# Smarty-TOP.net
KiCad netlist of a schematic drawn in EAGLE
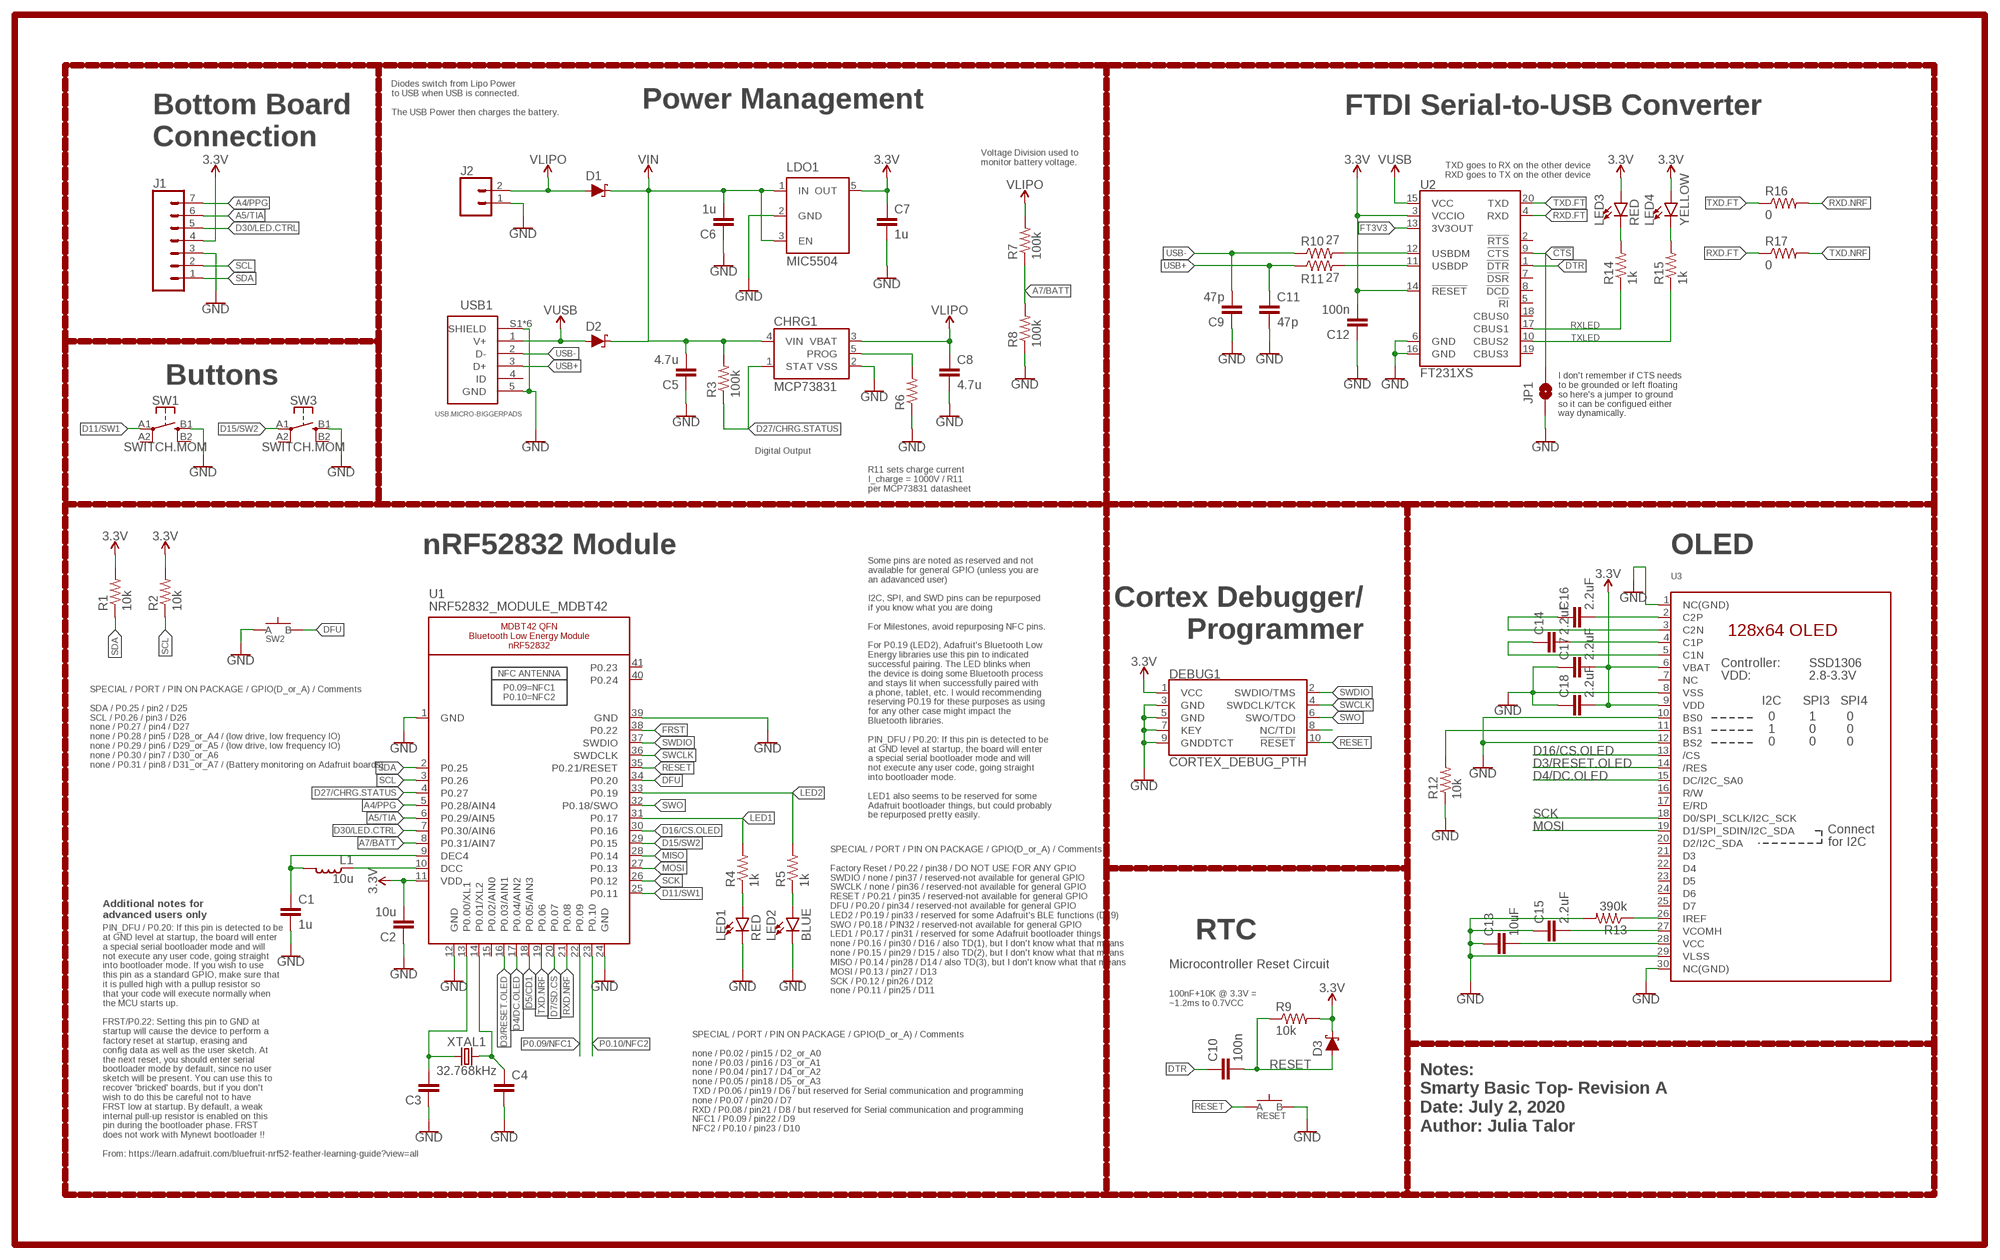
[diagram p0: schematic, sheet 1]

(export (version "E")
  (design (tool "Eeschema 10.0.6"))
  (components
    (comp (ref "C1")
      (value "1u")
      (footprint "eagle-import:C0603")
      (libsource (lib "eagle-import") (part "CAPACITOR0603"))
    )
    (comp (ref "C2")
      (value "10u")
      (footprint "eagle-import:C0805")
      (libsource (lib "eagle-import") (part "CAPACITOR0805"))
    )
    (comp (ref "C3")
      (value "CAPACITOR0603")
      (footprint "eagle-import:C0603")
      (libsource (lib "eagle-import") (part "CAPACITOR0603"))
    )
    (comp (ref "C4")
      (value "CAPACITOR0603")
      (footprint "eagle-import:C0603")
      (libsource (lib "eagle-import") (part "CAPACITOR0603"))
    )
    (comp (ref "C5")
      (value "4.7u")
      (footprint "eagle-import:C0603")
      (libsource (lib "eagle-import") (part "CAPACITOR0603"))
    )
    (comp (ref "C6")
      (value "1u")
      (footprint "eagle-import:C0603")
      (libsource (lib "eagle-import") (part "CAPACITOR0603"))
    )
    (comp (ref "C7")
      (value "1u")
      (footprint "eagle-import:C0603")
      (libsource (lib "eagle-import") (part "CAPACITOR0603"))
    )
    (comp (ref "C8")
      (value "4.7u")
      (footprint "eagle-import:C0603")
      (libsource (lib "eagle-import") (part "CAPACITOR0603"))
    )
    (comp (ref "C9")
      (value "47p")
      (footprint "eagle-import:C0603")
      (libsource (lib "eagle-import") (part "CAPACITOR0603"))
    )
    (comp (ref "C10")
      (value "100n")
      (footprint "eagle-import:C0603")
      (libsource (lib "eagle-import") (part "CAPACITOR0603"))
    )
    (comp (ref "C11")
      (value "47p")
      (footprint "eagle-import:C0603")
      (libsource (lib "eagle-import") (part "CAPACITOR0603"))
    )
    (comp (ref "C12")
      (value "100n")
      (footprint "eagle-import:C0603")
      (libsource (lib "eagle-import") (part "CAPACITOR0603"))
    )
    (comp (ref "C13")
      (value "10uF")
      (footprint "eagle-import:C0603")
      (libsource (lib "eagle-import") (part "CAPACITOR0603"))
    )
    (comp (ref "C14")
      (value "2.2uF")
      (footprint "eagle-import:C0402")
      (libsource (lib "eagle-import") (part "CAPACITOR0402"))
    )
    (comp (ref "C15")
      (value "2.2uF")
      (footprint "eagle-import:C0603")
      (libsource (lib "eagle-import") (part "CAPACITOR0603"))
    )
    (comp (ref "C16")
      (value "2.2uF")
      (footprint "eagle-import:C0402")
      (libsource (lib "eagle-import") (part "CAPACITOR0402"))
    )
    (comp (ref "C17")
      (value "2.2uF")
      (footprint "eagle-import:C0402")
      (libsource (lib "eagle-import") (part "CAPACITOR0402"))
    )
    (comp (ref "C18")
      (value "2.2uF")
      (footprint "eagle-import:C0402")
      (libsource (lib "eagle-import") (part "CAPACITOR0402"))
    )
    (comp (ref "CHRG1")
      (value "MCP73831")
      (footprint "eagle-import:SOT23-5")
      (libsource (lib "eagle-import") (part "MCP73831"))
    )
    (comp (ref "D1")
      (value "SCHOTTKY-USC")
      (footprint "eagle-import:USC")
      (libsource (lib "eagle-import") (part "SCHOTTKY-USC"))
    )
    (comp (ref "D2")
      (value "SCHOTTKY-USC")
      (footprint "eagle-import:USC")
      (libsource (lib "eagle-import") (part "SCHOTTKY-USC"))
    )
    (comp (ref "D3")
      (value "SCHOTTKY-USC")
      (footprint "eagle-import:USC")
      (libsource (lib "eagle-import") (part "SCHOTTKY-USC"))
    )
    (comp (ref "DEBUG1")
      (value "CORTEX_DEBUG_PTH")
      (footprint "eagle-import:2X5-PTH-1.27MM")
      (libsource (lib "eagle-import") (part "CORTEX_DEBUG_PTH"))
    )
    (comp (ref "J1")
      (value "CONN_07-1.27MM")
      (footprint "eagle-import:1X07_1.27MM")
      (libsource (lib "eagle-import") (part "CONN_07-1.27MM"))
    )
    (comp (ref "J2")
      (value "CONN_02")
      (footprint "eagle-import:1X02")
      (libsource (lib "eagle-import") (part "CONN_02"))
    )
    (comp (ref "JP1")
      (value "JUMPER-SMT_2_NO_SILK")
      (footprint "eagle-import:SMT-JUMPER_2_NO_SILK")
      (libsource (lib "eagle-import") (part "JUMPER-SMT_2_NO_SILK"))
    )
    (comp (ref "L1")
      (value "10u")
      (footprint "eagle-import:L0603")
      (libsource (lib "eagle-import") (part "INDUCTOR0603"))
    )
    (comp (ref "LDO1")
      (value "MIC5504")
      (footprint "eagle-import:SOT23-5")
      (libsource (lib "eagle-import") (part "MIC5504"))
    )
    (comp (ref "LED1")
      (value "RED")
      (footprint "eagle-import:LED-0603")
      (libsource (lib "eagle-import") (part "LED0603"))
    )
    (comp (ref "LED2")
      (value "BLUE")
      (footprint "eagle-import:LED-0603")
      (libsource (lib "eagle-import") (part "LED0603"))
    )
    (comp (ref "LED3")
      (value "RED")
      (footprint "eagle-import:LED-0603")
      (libsource (lib "eagle-import") (part "LED0603"))
    )
    (comp (ref "LED4")
      (value "YELLOW")
      (footprint "eagle-import:LED-0603")
      (libsource (lib "eagle-import") (part "LED0603"))
    )
    (comp (ref "R1")
      (value "10k")
      (footprint "eagle-import:R0603")
      (libsource (lib "eagle-import") (part "RESISTOR0603"))
    )
    (comp (ref "R2")
      (value "10k")
      (footprint "eagle-import:R0603")
      (libsource (lib "eagle-import") (part "RESISTOR0603"))
    )
    (comp (ref "R3")
      (value "100k")
      (footprint "eagle-import:R0603")
      (libsource (lib "eagle-import") (part "RESISTOR0603"))
    )
    (comp (ref "R4")
      (value "1k")
      (footprint "eagle-import:R0603")
      (libsource (lib "eagle-import") (part "RESISTOR0603"))
    )
    (comp (ref "R5")
      (value "1k")
      (footprint "eagle-import:R0603")
      (libsource (lib "eagle-import") (part "RESISTOR0603"))
    )
    (comp (ref "R6")
      (value "RESISTOR0603")
      (footprint "eagle-import:R0603")
      (libsource (lib "eagle-import") (part "RESISTOR0603"))
    )
    (comp (ref "R7")
      (value "100k")
      (footprint "eagle-import:R0603")
      (libsource (lib "eagle-import") (part "RESISTOR0603"))
    )
    (comp (ref "R8")
      (value "100k")
      (footprint "eagle-import:R0603")
      (libsource (lib "eagle-import") (part "RESISTOR0603"))
    )
    (comp (ref "R9")
      (value "10k")
      (footprint "eagle-import:R0603")
      (libsource (lib "eagle-import") (part "RESISTOR0603"))
    )
    (comp (ref "R10")
      (value "27")
      (footprint "eagle-import:R0603")
      (libsource (lib "eagle-import") (part "RESISTOR0603"))
    )
    (comp (ref "R11")
      (value "27")
      (footprint "eagle-import:R0603")
      (libsource (lib "eagle-import") (part "RESISTOR0603"))
    )
    (comp (ref "R12")
      (value "10k")
      (footprint "eagle-import:R0603")
      (libsource (lib "eagle-import") (part "RESISTOR0603"))
    )
    (comp (ref "R13")
      (value "390k")
      (footprint "eagle-import:R0603")
      (libsource (lib "eagle-import") (part "RESISTOR0603"))
    )
    (comp (ref "R14")
      (value "1k")
      (footprint "eagle-import:R0603")
      (libsource (lib "eagle-import") (part "RESISTOR0603"))
    )
    (comp (ref "R15")
      (value "1k")
      (footprint "eagle-import:R0603")
      (libsource (lib "eagle-import") (part "RESISTOR0603"))
    )
    (comp (ref "R16")
      (value "0")
      (footprint "eagle-import:R0603")
      (libsource (lib "eagle-import") (part "RESISTOR0603"))
    )
    (comp (ref "R17")
      (value "0")
      (footprint "eagle-import:R0603")
      (libsource (lib "eagle-import") (part "RESISTOR0603"))
    )
    (comp (ref "RESET")
      (value "SPST-PTS830GG140-COPY.1-3")
      (footprint "eagle-import:BUTTON-GULLWING")
      (libsource (lib "eagle-import") (part "SPST-PTS830GG140-COPY.1-3"))
    )
    (comp (ref "SW1")
      (value "SWITCH.MOM")
      (footprint "eagle-import:TACTILE_SWITCH_SMD_6.2MM_TALL")
      (libsource (lib "eagle-import") (part "SWITCH.MOM"))
    )
    (comp (ref "SW2")
      (value "SPST-PTS830GG140-COPY.1-3")
      (footprint "eagle-import:BUTTON-GULLWING")
      (libsource (lib "eagle-import") (part "SPST-PTS830GG140-COPY.1-3"))
    )
    (comp (ref "SW3")
      (value "SWITCH.MOM")
      (footprint "eagle-import:TACTILE_SWITCH_SMD_6.2MM_TALL")
      (libsource (lib "eagle-import") (part "SWITCH.MOM"))
    )
    (comp (ref "U1")
      (value "NRF52832_MODULE_MDBT42")
      (footprint "eagle-import:BLE_MODULE_RAYTAC_MDBT42")
      (libsource (lib "eagle-import") (part "NRF52832_MODULE_MDBT42"))
    )
    (comp (ref "U2")
      (value "FT231XS")
      (footprint "eagle-import:SSOP20_L")
      (libsource (lib "eagle-import") (part "FT231XS"))
    )
    (comp (ref "U3")
      (value "DISP_OLED_UG-2864HSWEG01-NO-WRAPAROUND")
      (footprint "eagle-import:UG-2864HSWEG01_0.96IN_NO-WRAPAROUND")
      (libsource (lib "eagle-import") (part "DISP_OLED_UG-2864HSWEG01-NO-WRAPAROUND"))
    )
    (comp (ref "USB1")
      (value "USB.MICRO-BIGGERPADS")
      (footprint "eagle-import:USB-MICRO-01.BIGGERPADS")
      (libsource (lib "eagle-import") (part "USB.MICRO-BIGGERPADS"))
    )
    (comp (ref "XTAL1")
      (value "32.768kHz")
      (footprint "eagle-import:2-SMD.NOLEAD.2.0MMTO1.2MM")
      (libsource (lib "eagle-import") (part "CRYSTALECS-.327-12.5-12-C-TR"))
    )
  )
  (nets
    (net (code "1") (name "/RXLED") (class "Default")
      (node (ref "R14") (pin "1") (pinfunction "1_1") (pintype "passive"))
      (node (ref "U2") (pin "17") (pinfunction "CBUS1_17") (pintype "bidirectional"))
    )
    (net (code "2") (name "/TXLED") (class "Default")
      (node (ref "R15") (pin "1") (pinfunction "1_1") (pintype "passive"))
      (node (ref "U2") (pin "10") (pinfunction "CBUS2_10") (pintype "bidirectional"))
    )
    (net (code "3") (name "/~{CTS}") (class "Default")
      (node (ref "JP1") (pin "2") (pinfunction "2_2") (pintype "passive"))
      (node (ref "U2") (pin "9") (pinfunction "~{CTS}_9") (pintype "bidirectional"))
    )
    (net (code "4") (name "3.3V") (class "Default")
      (node (ref "C12") (pin "2") (pinfunction "2_2") (pintype "passive"))
      (node (ref "C17") (pin "2") (pinfunction "2_2") (pintype "passive"))
      (node (ref "C18") (pin "2") (pinfunction "2_2") (pintype "passive"))
      (node (ref "C2") (pin "2") (pinfunction "2_2") (pintype "passive"))
      (node (ref "C7") (pin "1") (pinfunction "1_1") (pintype "passive"))
      (node (ref "D3") (pin "-") (pinfunction "C_-") (pintype "passive"))
      (node (ref "DEBUG1") (pin "1") (pinfunction "VCC_1") (pintype "bidirectional"))
      (node (ref "J1") (pin "4") (pinfunction "4_4") (pintype "passive"))
      (node (ref "LDO1") (pin "5") (pinfunction "OUT_5") (pintype "bidirectional"))
      (node (ref "LED3") (pin "A") (pinfunction "A_A") (pintype "passive"))
      (node (ref "LED4") (pin "A") (pinfunction "A_A") (pintype "passive"))
      (node (ref "R1") (pin "2") (pinfunction "2_2") (pintype "passive"))
      (node (ref "R2") (pin "2") (pinfunction "2_2") (pintype "passive"))
      (node (ref "R9") (pin "2") (pinfunction "2_2") (pintype "passive"))
      (node (ref "U1") (pin "11") (pinfunction "VDD_11") (pintype "bidirectional"))
      (node (ref "U2") (pin "14") (pinfunction "~{RESET}_14") (pintype "bidirectional"))
      (node (ref "U2") (pin "3") (pinfunction "VCCIO_3") (pintype "bidirectional"))
      (node (ref "U3") (pin "6") (pinfunction "VBAT_6") (pintype "input"))
      (node (ref "U3") (pin "9") (pinfunction "VDD_9") (pintype "power_in"))
    )
    (net (code "5") (name "A4{slash}PPG") (class "Default")
      (node (ref "J1") (pin "7") (pinfunction "7_7") (pintype "passive"))
      (node (ref "U1") (pin "5") (pinfunction "P0.28/AIN4_5") (pintype "bidirectional"))
    )
    (net (code "6") (name "A5{slash}TIA") (class "Default")
      (node (ref "J1") (pin "6") (pinfunction "6_6") (pintype "passive"))
      (node (ref "U1") (pin "6") (pinfunction "P0.29/AIN5_6") (pintype "bidirectional"))
    )
    (net (code "7") (name "A7{slash}BATT") (class "Default")
      (node (ref "R7") (pin "1") (pinfunction "1_1") (pintype "passive"))
      (node (ref "R8") (pin "2") (pinfunction "2_2") (pintype "passive"))
      (node (ref "U1") (pin "8") (pinfunction "P0.31/AIN7_8") (pintype "bidirectional"))
    )
    (net (code "8") (name "D3{slash}RESET.OLED") (class "Default")
      (node (ref "U1") (pin "16") (pinfunction "P0.03/AIN1_16") (pintype "bidirectional"))
      (node (ref "U3") (pin "14") (pinfunction "/RES_14") (pintype "input"))
    )
    (net (code "9") (name "D4{slash}DC.OLED") (class "Default")
      (node (ref "U1") (pin "17") (pinfunction "P0.04/AIN2_17") (pintype "bidirectional"))
      (node (ref "U3") (pin "15") (pinfunction "DC/I2C_SA0_15") (pintype "input"))
    )
    (net (code "10") (name "D5{slash}CD1") (class "Default")
      (node (ref "U1") (pin "18") (pinfunction "P0.05/AIN3_18") (pintype "bidirectional"))
    )
    (net (code "11") (name "D7{slash}SD.CS") (class "Default")
      (node (ref "U1") (pin "20") (pinfunction "P0.07_20") (pintype "bidirectional"))
    )
    (net (code "12") (name "D11{slash}SW1") (class "Default")
      (node (ref "SW1") (pin "A1") (pinfunction "1_A1") (pintype "passive"))
      (node (ref "U1") (pin "25") (pinfunction "P0.11_25") (pintype "bidirectional"))
    )
    (net (code "13") (name "D15{slash}SW2") (class "Default")
      (node (ref "SW3") (pin "A1") (pinfunction "1_A1") (pintype "passive"))
      (node (ref "U1") (pin "29") (pinfunction "P0.15_29") (pintype "bidirectional"))
    )
    (net (code "14") (name "D16{slash}CS.OLED") (class "Default")
      (node (ref "U1") (pin "30") (pinfunction "P0.16_30") (pintype "bidirectional"))
      (node (ref "U3") (pin "13") (pinfunction "/CS_13") (pintype "input"))
    )
    (net (code "15") (name "D27{slash}CHRG.STATUS") (class "Default")
      (node (ref "CHRG1") (pin "1") (pinfunction "STAT_1") (pintype "output"))
      (node (ref "R3") (pin "1") (pinfunction "1_1") (pintype "passive"))
      (node (ref "U1") (pin "4") (pinfunction "P0.27_4") (pintype "bidirectional"))
    )
    (net (code "16") (name "D30{slash}LED.CTRL") (class "Default")
      (node (ref "J1") (pin "5") (pinfunction "5_5") (pintype "passive"))
      (node (ref "U1") (pin "7") (pinfunction "P0.30/AIN6_7") (pintype "bidirectional"))
    )
    (net (code "17") (name "DFU") (class "Default")
      (node (ref "SW2") (pin "3") (pinfunction "B_3") (pintype "bidirectional"))
      (node (ref "U1") (pin "34") (pinfunction "P0.20_34") (pintype "bidirectional"))
    )
    (net (code "18") (name "DTR") (class "Default")
      (node (ref "C10") (pin "1") (pinfunction "1_1") (pintype "passive"))
      (node (ref "U2") (pin "1") (pinfunction "~{DTR}_1") (pintype "bidirectional"))
    )
    (net (code "19") (name "FRST") (class "Default")
      (node (ref "U1") (pin "38") (pinfunction "P0.22_38") (pintype "bidirectional"))
    )
    (net (code "20") (name "FT3V3") (class "Default")
      (node (ref "U2") (pin "13") (pinfunction "3V3OUT_13") (pintype "bidirectional"))
    )
    (net (code "21") (name "GND") (class "Default")
      (node (ref "C1") (pin "2") (pinfunction "2_2") (pintype "passive"))
      (node (ref "C11") (pin "2") (pinfunction "2_2") (pintype "passive"))
      (node (ref "C12") (pin "1") (pinfunction "1_1") (pintype "passive"))
      (node (ref "C13") (pin "1") (pinfunction "1_1") (pintype "passive"))
      (node (ref "C15") (pin "1") (pinfunction "1_1") (pintype "passive"))
      (node (ref "C17") (pin "1") (pinfunction "1_1") (pintype "passive"))
      (node (ref "C18") (pin "1") (pinfunction "1_1") (pintype "passive"))
      (node (ref "C2") (pin "1") (pinfunction "1_1") (pintype "passive"))
      (node (ref "C3") (pin "1") (pinfunction "1_1") (pintype "passive"))
      (node (ref "C4") (pin "2") (pinfunction "2_2") (pintype "passive"))
      (node (ref "C5") (pin "1") (pinfunction "1_1") (pintype "passive"))
      (node (ref "C6") (pin "1") (pinfunction "1_1") (pintype "passive"))
      (node (ref "C7") (pin "2") (pinfunction "2_2") (pintype "passive"))
      (node (ref "C8") (pin "2") (pinfunction "2_2") (pintype "passive"))
      (node (ref "C9") (pin "1") (pinfunction "1_1") (pintype "passive"))
      (node (ref "CHRG1") (pin "2") (pinfunction "VSS_2") (pintype "power_in"))
      (node (ref "DEBUG1") (pin "3") (pinfunction "GND_3") (pintype "bidirectional"))
      (node (ref "DEBUG1") (pin "5") (pinfunction "GND_5") (pintype "bidirectional"))
      (node (ref "DEBUG1") (pin "7") (pinfunction "KEY_7") (pintype "bidirectional"))
      (node (ref "DEBUG1") (pin "9") (pinfunction "GNDDTCT_9") (pintype "bidirectional"))
      (node (ref "J1") (pin "3") (pinfunction "3_3") (pintype "passive"))
      (node (ref "J2") (pin "1") (pinfunction "1_1") (pintype "passive"))
      (node (ref "JP1") (pin "1") (pinfunction "1_1") (pintype "passive"))
      (node (ref "LDO1") (pin "2") (pinfunction "GND_2") (pintype "bidirectional"))
      (node (ref "LED1") (pin "C") (pinfunction "C_C") (pintype "passive"))
      (node (ref "LED2") (pin "C") (pinfunction "C_C") (pintype "passive"))
      (node (ref "R12") (pin "1") (pinfunction "1_1") (pintype "passive"))
      (node (ref "R13") (pin "2") (pinfunction "2_2") (pintype "passive"))
      (node (ref "R6") (pin "1") (pinfunction "1_1") (pintype "passive"))
      (node (ref "R8") (pin "1") (pinfunction "1_1") (pintype "passive"))
      (node (ref "RESET") (pin "3") (pinfunction "B_3") (pintype "bidirectional"))
      (node (ref "SW1") (pin "B1") (pinfunction "3_B1") (pintype "passive"))
      (node (ref "SW2") (pin "1") (pinfunction "A_1") (pintype "bidirectional"))
      (node (ref "SW3") (pin "B1") (pinfunction "3_B1") (pintype "passive"))
      (node (ref "U1") (pin "1") (pinfunction "GND_1") (pintype "bidirectional"))
      (node (ref "U1") (pin "12") (pinfunction "GND_12") (pintype "bidirectional"))
      (node (ref "U1") (pin "24") (pinfunction "GND_24") (pintype "bidirectional"))
      (node (ref "U1") (pin "39") (pinfunction "GND_39") (pintype "bidirectional"))
      (node (ref "U2") (pin "16") (pinfunction "GND_16") (pintype "bidirectional"))
      (node (ref "U2") (pin "6") (pinfunction "GND_6") (pintype "bidirectional"))
      (node (ref "U3") (pin "1") (pinfunction "NC(GND)_1") (pintype "input"))
      (node (ref "U3") (pin "10") (pinfunction "BS0_10") (pintype "input"))
      (node (ref "U3") (pin "12") (pinfunction "BS2_12") (pintype "input"))
      (node (ref "U3") (pin "29") (pinfunction "VLSS_29") (pintype "power_in"))
      (node (ref "U3") (pin "30") (pinfunction "NC(GND)_30") (pintype "input"))
      (node (ref "U3") (pin "8") (pinfunction "VSS_8") (pintype "power_in"))
      (node (ref "USB1") (pin "5") (pinfunction "GND_5") (pintype "bidirectional"))
      (node (ref "USB1") (pin "S1") (pinfunction "SHIELD_S1") (pintype "bidirectional"))
      (node (ref "USB1") (pin "S2") (pinfunction "SHIELD_S2") (pintype "bidirectional"))
      (node (ref "USB1") (pin "S3") (pinfunction "SHIELD_S3") (pintype "bidirectional"))
      (node (ref "USB1") (pin "S4") (pinfunction "SHIELD_S4") (pintype "bidirectional"))
      (node (ref "USB1") (pin "S5") (pinfunction "SHIELD_S5") (pintype "bidirectional"))
      (node (ref "USB1") (pin "S6") (pinfunction "SHIELD_S6") (pintype "bidirectional"))
    )
    (net (code "22") (name "LED1") (class "Default")
      (node (ref "R4") (pin "2") (pinfunction "2_2") (pintype "passive"))
      (node (ref "U1") (pin "31") (pinfunction "P0.17_31") (pintype "bidirectional"))
    )
    (net (code "23") (name "LED2") (class "Default")
      (node (ref "R5") (pin "2") (pinfunction "2_2") (pintype "passive"))
      (node (ref "U1") (pin "33") (pinfunction "P0.19_33") (pintype "bidirectional"))
    )
    (net (code "24") (name "MISO") (class "Default")
      (node (ref "U1") (pin "28") (pinfunction "P0.14_28") (pintype "bidirectional"))
    )
    (net (code "25") (name "MOSI") (class "Default")
      (node (ref "U1") (pin "27") (pinfunction "P0.13_27") (pintype "bidirectional"))
      (node (ref "U3") (pin "19") (pinfunction "D1/SPI_SDIN/I2C_SDA_19") (pintype "bidirectional"))
    )
    (net (code "26") (name "Net-(CHRG1-PROG)") (class "Default")
      (node (ref "CHRG1") (pin "5") (pinfunction "PROG_5") (pintype "input"))
      (node (ref "R6") (pin "2") (pinfunction "2_2") (pintype "passive"))
    )
    (net (code "27") (name "Net-(LED1-PadA)") (class "Default")
      (node (ref "LED1") (pin "A") (pinfunction "A_A") (pintype "passive"))
      (node (ref "R4") (pin "1") (pinfunction "1_1") (pintype "passive"))
    )
    (net (code "28") (name "Net-(LED2-PadA)") (class "Default")
      (node (ref "LED2") (pin "A") (pinfunction "A_A") (pintype "passive"))
      (node (ref "R5") (pin "1") (pinfunction "1_1") (pintype "passive"))
    )
    (net (code "29") (name "Net-(LED3-PadC)") (class "Default")
      (node (ref "LED3") (pin "C") (pinfunction "C_C") (pintype "passive"))
      (node (ref "R14") (pin "2") (pinfunction "2_2") (pintype "passive"))
    )
    (net (code "30") (name "Net-(LED4-PadC)") (class "Default")
      (node (ref "LED4") (pin "C") (pinfunction "C_C") (pintype "passive"))
      (node (ref "R15") (pin "2") (pinfunction "2_2") (pintype "passive"))
    )
    (net (code "31") (name "Net-(U1-DCC)") (class "Default")
      (node (ref "L1") (pin "1") (pinfunction "1_1") (pintype "passive"))
      (node (ref "U1") (pin "10") (pinfunction "DCC_10") (pintype "bidirectional"))
    )
    (net (code "32") (name "Net-(U1-DEC4)") (class "Default")
      (node (ref "C1") (pin "1") (pinfunction "1_1") (pintype "passive"))
      (node (ref "L1") (pin "2") (pinfunction "2_2") (pintype "passive"))
      (node (ref "U1") (pin "9") (pinfunction "DEC4_9") (pintype "bidirectional"))
    )
    (net (code "33") (name "Net-(U1-P0.00{slash}XL1)") (class "Default")
      (node (ref "C3") (pin "2") (pinfunction "2_2") (pintype "passive"))
      (node (ref "U1") (pin "13") (pinfunction "P0.00/XL1_13") (pintype "bidirectional"))
      (node (ref "XTAL1") (pin "P$1") (pinfunction "1_P$1") (pintype "passive"))
    )
    (net (code "34") (name "Net-(U1-P0.01{slash}XL2)") (class "Default")
      (node (ref "C4") (pin "1") (pinfunction "1_1") (pintype "passive"))
      (node (ref "U1") (pin "14") (pinfunction "P0.01/XL2_14") (pintype "bidirectional"))
      (node (ref "XTAL1") (pin "P$2") (pinfunction "2_P$2") (pintype "passive"))
    )
    (net (code "35") (name "Net-(U2-USBDM)") (class "Default")
      (node (ref "R10") (pin "2") (pinfunction "2_2") (pintype "passive"))
      (node (ref "U2") (pin "12") (pinfunction "USBDM_12") (pintype "bidirectional"))
    )
    (net (code "36") (name "Net-(U2-USBDP)") (class "Default")
      (node (ref "R11") (pin "2") (pinfunction "2_2") (pintype "passive"))
      (node (ref "U2") (pin "11") (pinfunction "USBDP_11") (pintype "bidirectional"))
    )
    (net (code "37") (name "Net-(U3-BS1)") (class "Default")
      (node (ref "R12") (pin "2") (pinfunction "2_2") (pintype "passive"))
      (node (ref "U3") (pin "11") (pinfunction "BS1_11") (pintype "input"))
    )
    (net (code "38") (name "Net-(U3-C1N)") (class "Default")
      (node (ref "C14") (pin "1") (pinfunction "1_1") (pintype "passive"))
      (node (ref "U3") (pin "5") (pinfunction "C1N_5") (pintype "input"))
    )
    (net (code "39") (name "Net-(U3-C1P)") (class "Default")
      (node (ref "C14") (pin "2") (pinfunction "2_2") (pintype "passive"))
      (node (ref "U3") (pin "4") (pinfunction "C1P_4") (pintype "input"))
    )
    (net (code "40") (name "Net-(U3-C2N)") (class "Default")
      (node (ref "C16") (pin "1") (pinfunction "1_1") (pintype "passive"))
      (node (ref "U3") (pin "3") (pinfunction "C2N_3") (pintype "input"))
    )
    (net (code "41") (name "Net-(U3-C2P)") (class "Default")
      (node (ref "C16") (pin "2") (pinfunction "2_2") (pintype "passive"))
      (node (ref "U3") (pin "2") (pinfunction "C2P_2") (pintype "input"))
    )
    (net (code "42") (name "Net-(U3-IREF)") (class "Default")
      (node (ref "R13") (pin "1") (pinfunction "1_1") (pintype "passive"))
      (node (ref "U3") (pin "26") (pinfunction "IREF_26") (pintype "input"))
    )
    (net (code "43") (name "Net-(U3-VCC)") (class "Default")
      (node (ref "C13") (pin "2") (pinfunction "2_2") (pintype "passive"))
      (node (ref "U3") (pin "28") (pinfunction "VCC_28") (pintype "power_in"))
    )
    (net (code "44") (name "Net-(U3-VCOMH)") (class "Default")
      (node (ref "C15") (pin "2") (pinfunction "2_2") (pintype "passive"))
      (node (ref "U3") (pin "27") (pinfunction "VCOMH_27") (pintype "output"))
    )
    (net (code "45") (name "P0.09{slash}NFC1") (class "Default")
      (node (ref "U1") (pin "22") (pinfunction "P0.09_22") (pintype "bidirectional"))
    )
    (net (code "46") (name "P0.10{slash}NFC2") (class "Default")
      (node (ref "U1") (pin "23") (pinfunction "P0.10_23") (pintype "bidirectional"))
    )
    (net (code "47") (name "RESET") (class "Default")
      (node (ref "C10") (pin "2") (pinfunction "2_2") (pintype "passive"))
      (node (ref "D3") (pin "+") (pinfunction "A_+") (pintype "passive"))
      (node (ref "DEBUG1") (pin "10") (pinfunction "~{RESET}_10") (pintype "bidirectional"))
      (node (ref "R9") (pin "1") (pinfunction "1_1") (pintype "passive"))
      (node (ref "RESET") (pin "1") (pinfunction "A_1") (pintype "bidirectional"))
      (node (ref "U1") (pin "35") (pinfunction "P0.21/RESET_35") (pintype "bidirectional"))
    )
    (net (code "48") (name "RXD.FT") (class "Default")
      (node (ref "R17") (pin "1") (pinfunction "1_1") (pintype "passive"))
      (node (ref "U2") (pin "4") (pinfunction "RXD_4") (pintype "bidirectional"))
    )
    (net (code "49") (name "RXD.NRF") (class "Default")
      (node (ref "R16") (pin "2") (pinfunction "2_2") (pintype "passive"))
      (node (ref "U1") (pin "21") (pinfunction "P0.08_21") (pintype "bidirectional"))
    )
    (net (code "50") (name "SCK") (class "Default")
      (node (ref "U1") (pin "26") (pinfunction "P0.12_26") (pintype "bidirectional"))
      (node (ref "U3") (pin "18") (pinfunction "D0/SPI_SCLK/I2C_SCK_18") (pintype "bidirectional"))
    )
    (net (code "51") (name "SCL") (class "Default")
      (node (ref "J1") (pin "2") (pinfunction "2_2") (pintype "passive"))
      (node (ref "R2") (pin "1") (pinfunction "1_1") (pintype "passive"))
      (node (ref "U1") (pin "3") (pinfunction "P0.26_3") (pintype "bidirectional"))
    )
    (net (code "52") (name "SDA") (class "Default")
      (node (ref "J1") (pin "1") (pinfunction "1_1") (pintype "passive"))
      (node (ref "R1") (pin "1") (pinfunction "1_1") (pintype "passive"))
      (node (ref "U1") (pin "2") (pinfunction "P0.25_2") (pintype "bidirectional"))
    )
    (net (code "53") (name "SWCLK") (class "Default")
      (node (ref "DEBUG1") (pin "4") (pinfunction "SWDCLK/TCK_4") (pintype "bidirectional"))
      (node (ref "U1") (pin "36") (pinfunction "SWDCLK_36") (pintype "bidirectional"))
    )
    (net (code "54") (name "SWDIO") (class "Default")
      (node (ref "DEBUG1") (pin "2") (pinfunction "SWDIO/TMS_2") (pintype "bidirectional"))
      (node (ref "U1") (pin "37") (pinfunction "SWDIO_37") (pintype "bidirectional"))
    )
    (net (code "55") (name "SWO") (class "Default")
      (node (ref "DEBUG1") (pin "6") (pinfunction "SWO/TDO_6") (pintype "bidirectional"))
      (node (ref "U1") (pin "32") (pinfunction "P0.18/SWO_32") (pintype "bidirectional"))
    )
    (net (code "56") (name "TXD.FT") (class "Default")
      (node (ref "R16") (pin "1") (pinfunction "1_1") (pintype "passive"))
      (node (ref "U2") (pin "20") (pinfunction "TXD_20") (pintype "bidirectional"))
    )
    (net (code "57") (name "TXD.NRF") (class "Default")
      (node (ref "R17") (pin "2") (pinfunction "2_2") (pintype "passive"))
      (node (ref "U1") (pin "19") (pinfunction "P0.06_19") (pintype "bidirectional"))
    )
    (net (code "58") (name "USB+") (class "Default")
      (node (ref "C11") (pin "1") (pinfunction "1_1") (pintype "passive"))
      (node (ref "R11") (pin "1") (pinfunction "1_1") (pintype "passive"))
      (node (ref "USB1") (pin "3") (pinfunction "D+_3") (pintype "bidirectional"))
    )
    (net (code "59") (name "USB-") (class "Default")
      (node (ref "C9") (pin "2") (pinfunction "2_2") (pintype "passive"))
      (node (ref "R10") (pin "1") (pinfunction "1_1") (pintype "passive"))
      (node (ref "USB1") (pin "2") (pinfunction "D-_2") (pintype "bidirectional"))
    )
    (net (code "60") (name "VIN") (class "Default")
      (node (ref "C5") (pin "2") (pinfunction "2_2") (pintype "passive"))
      (node (ref "C6") (pin "2") (pinfunction "2_2") (pintype "passive"))
      (node (ref "CHRG1") (pin "4") (pinfunction "VIN_4") (pintype "power_in"))
      (node (ref "D1") (pin "-") (pinfunction "C_-") (pintype "passive"))
      (node (ref "D2") (pin "-") (pinfunction "C_-") (pintype "passive"))
      (node (ref "LDO1") (pin "1") (pinfunction "IN_1") (pintype "bidirectional"))
      (node (ref "LDO1") (pin "3") (pinfunction "EN_3") (pintype "bidirectional"))
      (node (ref "R3") (pin "2") (pinfunction "2_2") (pintype "passive"))
    )
    (net (code "61") (name "VLIPO") (class "Default")
      (node (ref "C8") (pin "1") (pinfunction "1_1") (pintype "passive"))
      (node (ref "CHRG1") (pin "3") (pinfunction "VBAT_3") (pintype "power_in"))
      (node (ref "D1") (pin "+") (pinfunction "A_+") (pintype "passive"))
      (node (ref "J2") (pin "2") (pinfunction "2_2") (pintype "passive"))
      (node (ref "R7") (pin "2") (pinfunction "2_2") (pintype "passive"))
    )
    (net (code "62") (name "VUSB") (class "Default")
      (node (ref "D2") (pin "+") (pinfunction "A_+") (pintype "passive"))
      (node (ref "U2") (pin "15") (pinfunction "VCC_15") (pintype "bidirectional"))
      (node (ref "USB1") (pin "1") (pinfunction "V+_1") (pintype "bidirectional"))
    )
    (net (code "63") (name "unconnected-(DEBUG1-NC{slash}TDI-Pad8)") (class "Default")
      (node (ref "DEBUG1") (pin "8") (pinfunction "NC/TDI_8") (pintype "bidirectional"))
    )
    (net (code "64") (name "unconnected-(SW1-2-PadA2)") (class "Default")
      (node (ref "SW1") (pin "A2") (pinfunction "2_A2") (pintype "passive"))
    )
    (net (code "65") (name "unconnected-(SW1-4-PadB2)") (class "Default")
      (node (ref "SW1") (pin "B2") (pinfunction "4_B2") (pintype "passive"))
    )
    (net (code "66") (name "unconnected-(SW3-2-PadA2)") (class "Default")
      (node (ref "SW3") (pin "A2") (pinfunction "2_A2") (pintype "passive"))
    )
    (net (code "67") (name "unconnected-(SW3-4-PadB2)") (class "Default")
      (node (ref "SW3") (pin "B2") (pinfunction "4_B2") (pintype "passive"))
    )
    (net (code "68") (name "unconnected-(U1-P0.02{slash}AIN0-Pad15)") (class "Default")
      (node (ref "U1") (pin "15") (pinfunction "P0.02/AIN0_15") (pintype "bidirectional"))
    )
    (net (code "69") (name "unconnected-(U1-P0.23-Pad41)") (class "Default")
      (node (ref "U1") (pin "41") (pinfunction "P0.23_41") (pintype "bidirectional"))
    )
    (net (code "70") (name "unconnected-(U1-P0.24-Pad40)") (class "Default")
      (node (ref "U1") (pin "40") (pinfunction "P0.24_40") (pintype "bidirectional"))
    )
    (net (code "71") (name "unconnected-(U2-CBUS0-Pad18)") (class "Default")
      (node (ref "U2") (pin "18") (pinfunction "CBUS0_18") (pintype "bidirectional"))
    )
    (net (code "72") (name "unconnected-(U2-CBUS3-Pad19)") (class "Default")
      (node (ref "U2") (pin "19") (pinfunction "CBUS3_19") (pintype "bidirectional"))
    )
    (net (code "73") (name "unconnected-(U2-~{DCD}-Pad8)") (class "Default")
      (node (ref "U2") (pin "8") (pinfunction "~{DCD}_8") (pintype "bidirectional"))
    )
    (net (code "74") (name "unconnected-(U2-~{DSR}-Pad7)") (class "Default")
      (node (ref "U2") (pin "7") (pinfunction "~{DSR}_7") (pintype "bidirectional"))
    )
    (net (code "75") (name "unconnected-(U2-~{RI}-Pad5)") (class "Default")
      (node (ref "U2") (pin "5") (pinfunction "~{RI}_5") (pintype "bidirectional"))
    )
    (net (code "76") (name "unconnected-(U2-~{RTS}-Pad2)") (class "Default")
      (node (ref "U2") (pin "2") (pinfunction "~{RTS}_2") (pintype "bidirectional"))
    )
    (net (code "77") (name "unconnected-(U3-D2{slash}I2C_SDA-Pad20)") (class "Default")
      (node (ref "U3") (pin "20") (pinfunction "D2/I2C_SDA_20") (pintype "bidirectional"))
    )
    (net (code "78") (name "unconnected-(U3-D3-Pad21)") (class "Default")
      (node (ref "U3") (pin "21") (pinfunction "D3_21") (pintype "bidirectional"))
    )
    (net (code "79") (name "unconnected-(U3-D4-Pad22)") (class "Default")
      (node (ref "U3") (pin "22") (pinfunction "D4_22") (pintype "bidirectional"))
    )
    (net (code "80") (name "unconnected-(U3-D5-Pad23)") (class "Default")
      (node (ref "U3") (pin "23") (pinfunction "D5_23") (pintype "bidirectional"))
    )
    (net (code "81") (name "unconnected-(U3-D6-Pad24)") (class "Default")
      (node (ref "U3") (pin "24") (pinfunction "D6_24") (pintype "bidirectional"))
    )
    (net (code "82") (name "unconnected-(U3-D7-Pad25)") (class "Default")
      (node (ref "U3") (pin "25") (pinfunction "D7_25") (pintype "bidirectional"))
    )
    (net (code "83") (name "unconnected-(U3-E{slash}RD-Pad17)") (class "Default")
      (node (ref "U3") (pin "17") (pinfunction "E/RD_17") (pintype "input"))
    )
    (net (code "84") (name "unconnected-(U3-NC-Pad7)") (class "Default")
      (node (ref "U3") (pin "7") (pinfunction "NC_7") (pintype "no_connect"))
    )
    (net (code "85") (name "unconnected-(U3-R{slash}W-Pad16)") (class "Default")
      (node (ref "U3") (pin "16") (pinfunction "R/W_16") (pintype "input"))
    )
    (net (code "86") (name "unconnected-(USB1-ID-Pad4)") (class "Default")
      (node (ref "USB1") (pin "4") (pinfunction "ID_4") (pintype "bidirectional"))
    )
  )
)
